# PAPI_M2_Control.net
KiCad netlist of a schematic drawn in Altium Designer
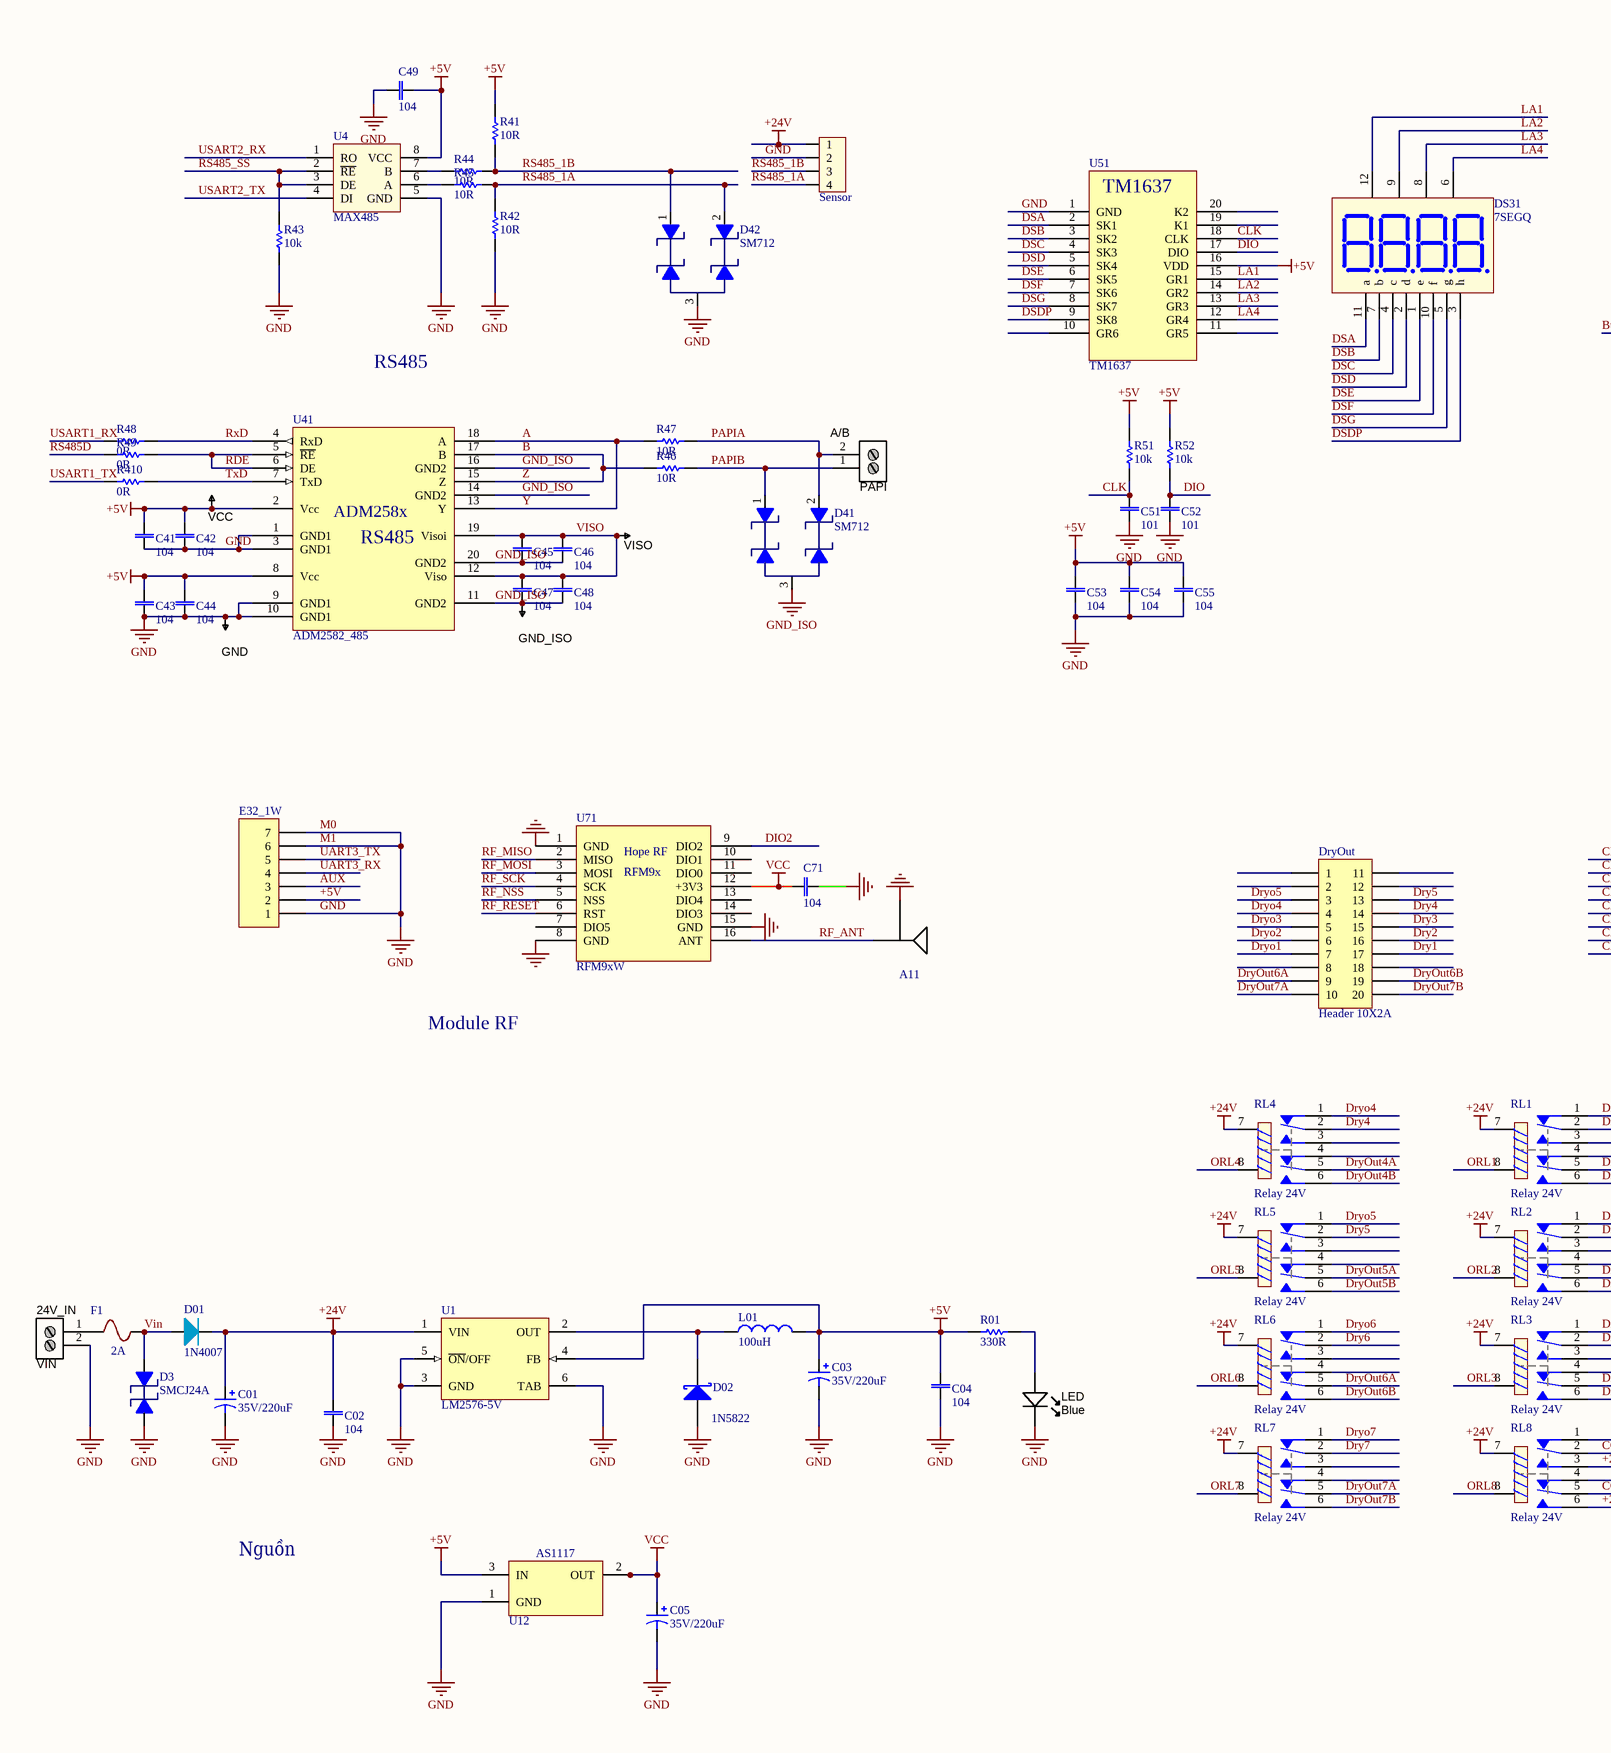
[diagram p0: PAPI_M2_Control.SchDoc, left]
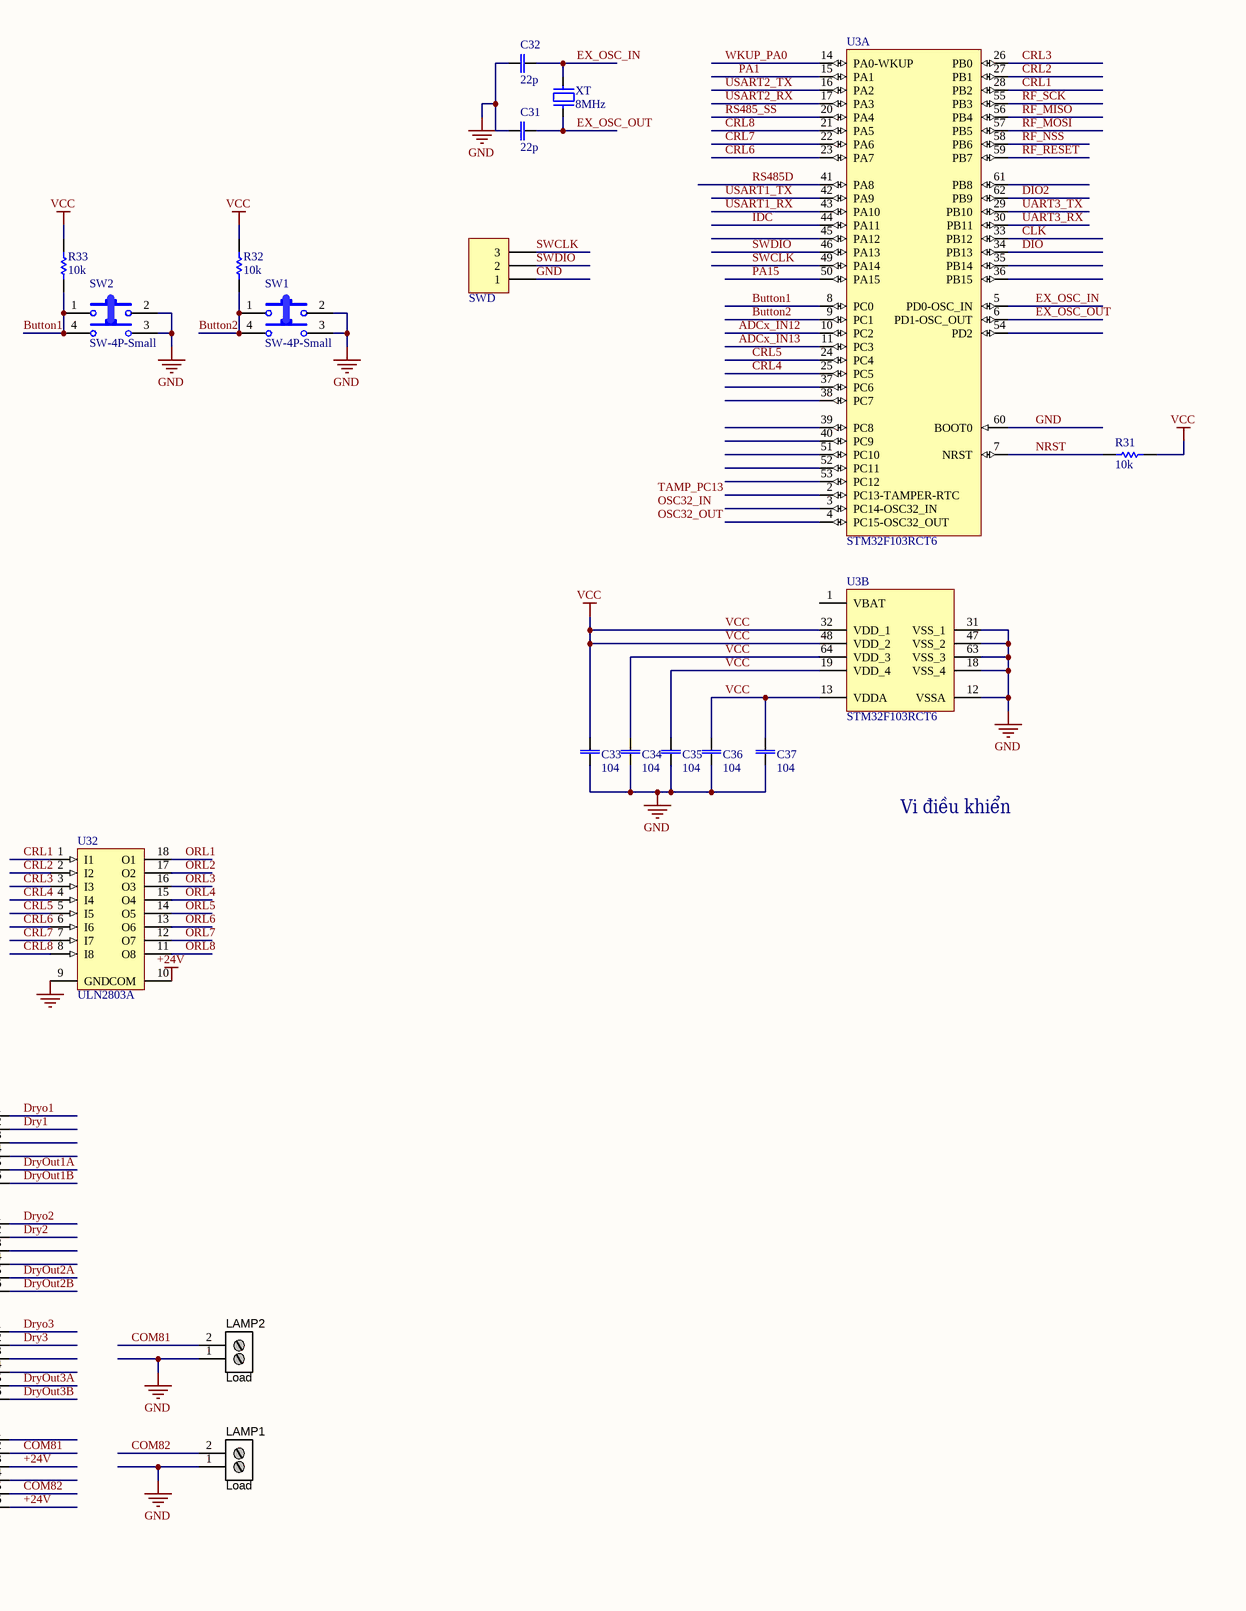
[diagram p1: PAPI_M2_Control.SchDoc, right]

(export (version "E")
  (design (tool "Eeschema 10.0.6"))
  (components
    (comp (ref "24V_IN")
      (value "VIN")
      (footprint "2P_PCB1")
      (description "Terminal Block Screw Type THT 2-Position 3.81mm pitch")
      (libsource (lib "") (part "2P_ScrewTerm_90S_3.81MM_1"))
    )
    (comp (ref "A11") (value "Giắc anten SMA") (footprint "SMA") (libsource (lib "Tuan") (part "RF_SMA")))
    (comp (ref "C01")
      (value "35V/220uF")
      (footprint "CAPE3.5-5.0MM_Rad_10x14mm")
      (fields (field (name "Comment") "Tụ nhôm cắm35V/220uF"))
      (libsource (lib "Tuan") (part "Cap"))
    )
    (comp (ref "C02")
      (value "104")
      (footprint "swatpcblib:CAP 0805")
      (description "Capacitor non polarized")
      (fields (field (name "Comment") "Tụ điện dán 0603104"))
      (libsource (lib "swatpcblib") (part "CAP NP"))
    )
    (comp (ref "C03")
      (value "35V/220uF")
      (footprint "CAPE3.5-5.0MM_Rad_10x14mm")
      (fields (field (name "Comment") "Tụ nhôm cắm35V/220uF"))
      (libsource (lib "Tuan") (part "Cap"))
    )
    (comp (ref "C04")
      (value "104")
      (footprint "swatpcblib:CAP 0805")
      (description "Capacitor non polarized")
      (fields (field (name "Comment") "Tụ điện dán 0603104"))
      (libsource (lib "swatpcblib") (part "CAP NP"))
    )
    (comp (ref "C05")
      (value "35V/220uF")
      (footprint "CAPE3.5-5.0MM_Rad_10x14mm")
      (fields (field (name "Comment") "Tụ nhôm cắm35V/220uF"))
      (libsource (lib "Tuan") (part "Cap"))
    )
    (comp (ref "C31")
      (value "22p")
      (footprint "swatpcblib:CAP 0805")
      (description "Capacitor non polarized")
      (fields (field (name "Comment") "Tụ điện dán 060322p"))
      (libsource (lib "swatpcblib") (part "CAP NP"))
    )
    (comp (ref "C32")
      (value "22p")
      (footprint "swatpcblib:CAP 0805")
      (description "Capacitor non polarized")
      (fields (field (name "Comment") "Tụ điện dán 060322p"))
      (libsource (lib "swatpcblib") (part "CAP NP"))
    )
    (comp (ref "C33")
      (value "104")
      (footprint "swatpcblib:CAP 0805")
      (description "Capacitor non polarized")
      (fields (field (name "Comment") "Tụ điện dán 0603104"))
      (libsource (lib "swatpcblib") (part "CAP NP"))
    )
    (comp (ref "C34")
      (value "104")
      (footprint "swatpcblib:CAP 0805")
      (description "Capacitor non polarized")
      (fields (field (name "Comment") "Tụ điện dán 0603104"))
      (libsource (lib "swatpcblib") (part "CAP NP"))
    )
    (comp (ref "C35")
      (value "104")
      (footprint "swatpcblib:CAP 0805")
      (description "Capacitor non polarized")
      (fields (field (name "Comment") "Tụ điện dán 0603104"))
      (libsource (lib "swatpcblib") (part "CAP NP"))
    )
    (comp (ref "C36")
      (value "104")
      (footprint "swatpcblib:CAP 0805")
      (description "Capacitor non polarized")
      (fields (field (name "Comment") "Tụ điện dán 0603104"))
      (libsource (lib "swatpcblib") (part "CAP NP"))
    )
    (comp (ref "C37")
      (value "104")
      (footprint "swatpcblib:CAP 0805")
      (description "Capacitor non polarized")
      (fields (field (name "Comment") "Tụ điện dán 0603104"))
      (libsource (lib "swatpcblib") (part "CAP NP"))
    )
    (comp (ref "C41")
      (value "104")
      (footprint "swatpcblib:CAP 0805")
      (description "Capacitor non polarized")
      (fields (field (name "Comment") "Tụ điện dán 0603104"))
      (libsource (lib "swatpcblib") (part "CAP NP"))
    )
    (comp (ref "C42")
      (value "104")
      (footprint "swatpcblib:CAP 0805")
      (description "Capacitor non polarized")
      (fields (field (name "Comment") "Tụ điện dán 0603104"))
      (libsource (lib "swatpcblib") (part "CAP NP"))
    )
    (comp (ref "C43")
      (value "104")
      (footprint "swatpcblib:CAP 0805")
      (description "Capacitor non polarized")
      (fields (field (name "Comment") "Tụ điện dán 0603104"))
      (libsource (lib "swatpcblib") (part "CAP NP"))
    )
    (comp (ref "C44")
      (value "104")
      (footprint "swatpcblib:CAP 0805")
      (description "Capacitor non polarized")
      (fields (field (name "Comment") "Tụ điện dán 0603104"))
      (libsource (lib "swatpcblib") (part "CAP NP"))
    )
    (comp (ref "C45")
      (value "104")
      (footprint "swatpcblib:CAP 0805")
      (description "Capacitor non polarized")
      (fields (field (name "Comment") "Tụ điện dán 0603104"))
      (libsource (lib "swatpcblib") (part "CAP NP"))
    )
    (comp (ref "C46")
      (value "104")
      (footprint "swatpcblib:CAP 0805")
      (description "Capacitor non polarized")
      (fields (field (name "Comment") "Tụ điện dán 0603104"))
      (libsource (lib "swatpcblib") (part "CAP NP"))
    )
    (comp (ref "C47")
      (value "104")
      (footprint "swatpcblib:CAP 0805")
      (description "Capacitor non polarized")
      (fields (field (name "Comment") "Tụ điện dán 0603104"))
      (libsource (lib "swatpcblib") (part "CAP NP"))
    )
    (comp (ref "C48")
      (value "104")
      (footprint "swatpcblib:CAP 0805")
      (description "Capacitor non polarized")
      (fields (field (name "Comment") "Tụ điện dán 0603104"))
      (libsource (lib "swatpcblib") (part "CAP NP"))
    )
    (comp (ref "C49")
      (value "104")
      (footprint "swatpcblib:CAP 0805")
      (description "Capacitor non polarized")
      (fields (field (name "Comment") "Tụ điện dán 0603104"))
      (libsource (lib "swatpcblib") (part "CAP NP"))
    )
    (comp (ref "C51")
      (value "101")
      (footprint "swatpcblib:CAP 0805")
      (description "Capacitor non polarized")
      (fields (field (name "Comment") "Tụ điện dán 0603101"))
      (libsource (lib "swatpcblib") (part "CAP NP"))
    )
    (comp (ref "C52")
      (value "101")
      (footprint "swatpcblib:CAP 0805")
      (description "Capacitor non polarized")
      (fields (field (name "Comment") "Tụ điện dán 0603101"))
      (libsource (lib "swatpcblib") (part "CAP NP"))
    )
    (comp (ref "C53")
      (value "104")
      (footprint "swatpcblib:CAP 0805")
      (description "Capacitor non polarized")
      (fields (field (name "Comment") "Tụ điện dán 0603104"))
      (libsource (lib "swatpcblib") (part "CAP NP"))
    )
    (comp (ref "C54")
      (value "104")
      (footprint "swatpcblib:CAP 0805")
      (description "Capacitor non polarized")
      (fields (field (name "Comment") "Tụ điện dán 0603104"))
      (libsource (lib "swatpcblib") (part "CAP NP"))
    )
    (comp (ref "C55")
      (value "104")
      (footprint "swatpcblib:CAP 0805")
      (description "Capacitor non polarized")
      (fields (field (name "Comment") "Tụ điện dán 0603104"))
      (libsource (lib "swatpcblib") (part "CAP NP"))
    )
    (comp (ref "C71")
      (value "104")
      (footprint "swatpcblib:CAP 0805")
      (description "Capacitor non polarized")
      (fields (field (name "Comment") "Tụ điện dán 0603104"))
      (libsource (lib "swatpcblib") (part "CAP NP"))
    )
    (comp (ref "D01")
      (value "Đi ốt cắm1N4007")
      (footprint "swatpcblib:DO-41")
      (fields (field (name "VL1") "1N4007"))
      (libsource (lib "swatpcblib") (part "Diode"))
    )
    (comp (ref "D02")
      (value "1N5822")
      (footprint "swatpcblib:DO-201")
      (description "Schottky Diodes Through Hole 3 A 40 V Schottky Diodes, DO-201AD, SB340 ,MBR340")
      (fields (field (name "Comment") "Đi ốt cắm1N5822"))
      (libsource (lib "swatpcblib") (part "Schottky Diodes"))
    )
    (comp (ref "D3")
      (value "SMCJ24A")
      (footprint "PBL - SMD Packages:DO-214AB")
      (description "ESD Suppressors / TVS Diodes 24volts 1.5kW 5% Uni-Dir. AEC-Q101")
      (libsource (lib "swatpcblib") (part "Diode Zenner"))
    )
    (comp (ref "D41") (value "SM712") (footprint "SOT23 TOP") (libsource (lib "Tuan") (part "SM712")))
    (comp (ref "D42") (value "SM712") (footprint "SOT23 TOP") (libsource (lib "Tuan") (part "SM712")))
    (comp (ref "DryOut")
      (value "Header 10X2A")
      (footprint "heromap:HDR2X10_CEN")
      (description "Header, 10-Pin, Dual row")
      (fields (field (name "PUBLISHER") "Altium Limited"))
      (libsource (lib "heromap") (part "Header 10X2A"))
    )
    (comp (ref "DS31")
      (value "7SEGQ")
      (footprint "heromap:7SEGQ")
      (description "Four 7 Seg Dipslay")
      (libsource (lib "heromap") (part "LED7Q"))
    )
    (comp (ref "E32_1W")
      (value "Header 7")
      (footprint "RF_AS32")
      (description "Header, 7-Pin")
      (fields (field (name "PUBLISHER") "Altium Limited"))
      (libsource (lib "Miscellaneous Connectors") (part "Header 7"))
    )
    (comp (ref "F1") (value "2A") (footprint "Fuse") (libsource (lib "Tuan") (part "Fuse")))
    (comp (ref "GND")
      (value "TESTPOINT")
      (footprint "TP-R60")
      (description "SMD test pin")
      (libsource (lib "PBL - Test Points") (part "TESTPOINT"))
    )
    (comp (ref "GND_ISO")
      (value "TESTPOINT")
      (footprint "TP-R60")
      (description "SMD test pin")
      (libsource (lib "PBL - Test Points") (part "TESTPOINT"))
    )
    (comp (ref "L01")
      (value "100uH")
      (footprint "Inductor 12x12x6")
      (fields (field (name "Comment") "Cuộn cảm dán100uH"))
      (libsource (lib "swatpcblib") (part "Inductor"))
    )
    (comp (ref "LAMP1")
      (value "Load")
      (footprint "2P_PCB1")
      (description "Terminal Block Screw Type THT 2-Position 3.81mm pitch")
      (libsource (lib "PBL - Connectors") (part "2P_ScrewTerm_90S_3.81MM"))
    )
    (comp (ref "LAMP2")
      (value "Load")
      (footprint "2P_PCB1")
      (description "Terminal Block Screw Type THT 2-Position 3.81mm pitch")
      (libsource (lib "PBL - Connectors") (part "2P_ScrewTerm_90S_3.81MM"))
    )
    (comp (ref "LED")
      (value "Blue")
      (footprint "LED-0805-K")
      (description "LED 0805 SMD Blue 100mcd 470nm")
      (fields (field (name "COLOR") "Blue"))
      (libsource (lib "PBL - Light Sources") (part "LED_SMD_Blue_0805_100mcd"))
    )
    (comp (ref "PAPI")
      (value "A/B")
      (footprint "2P_PCB1")
      (description "Terminal Block Screw Type THT 2-Position 3.81mm pitch")
      (libsource (lib "PBL - Connectors") (part "2P_ScrewTerm_90S_3.81MM"))
    )
    (comp (ref "R01")
      (value "330R")
      (footprint "swatpcblib:RES 0805")
      (description "Resistor")
      (fields (field (name "Comment") "Điện trở dán 0603330R"))
      (libsource (lib "swatpcblib") (part "Res"))
    )
    (comp (ref "R31")
      (value "10k")
      (footprint "swatpcblib:RES 0805")
      (description "Resistor")
      (fields (field (name "Comment") "Điện trở dán 060310k"))
      (libsource (lib "swatpcblib") (part "Res"))
    )
    (comp (ref "R32")
      (value "10k")
      (footprint "swatpcblib:RES 0805")
      (description "Resistor")
      (fields (field (name "Comment") "Điện trở dán 060310k"))
      (libsource (lib "swatpcblib") (part "Res"))
    )
    (comp (ref "R33")
      (value "10k")
      (footprint "swatpcblib:RES 0805")
      (description "Resistor")
      (fields (field (name "Comment") "Điện trở dán 060310k"))
      (libsource (lib "swatpcblib") (part "Res"))
    )
    (comp (ref "R41")
      (value "10R")
      (footprint "swatpcblib:RES 0805")
      (description "Resistor")
      (fields (field (name "Comment") "Điện trở dán 060310R"))
      (libsource (lib "swatpcblib") (part "Res"))
    )
    (comp (ref "R42")
      (value "10R")
      (footprint "swatpcblib:RES 0805")
      (description "Resistor")
      (fields (field (name "Comment") "Điện trở dán 060310R"))
      (libsource (lib "swatpcblib") (part "Res"))
    )
    (comp (ref "R43")
      (value "10k")
      (footprint "swatpcblib:RES 0805")
      (description "Resistor")
      (fields (field (name "Comment") "Điện trở dán 060310k"))
      (libsource (lib "swatpcblib") (part "Res"))
    )
    (comp (ref "R44")
      (value "10R")
      (footprint "swatpcblib:RES 0805")
      (description "Resistor")
      (fields (field (name "Comment") "Điện trở dán 060310R"))
      (libsource (lib "swatpcblib") (part "Res"))
    )
    (comp (ref "R45")
      (value "10R")
      (footprint "swatpcblib:RES 0805")
      (description "Resistor")
      (fields (field (name "Comment") "Điện trở dán 060310R"))
      (libsource (lib "swatpcblib") (part "Res"))
    )
    (comp (ref "R46")
      (value "10R")
      (footprint "swatpcblib:RES 0805")
      (description "Resistor")
      (fields (field (name "Comment") "Điện trở dán 060310R"))
      (libsource (lib "swatpcblib") (part "Res"))
    )
    (comp (ref "R47")
      (value "10R")
      (footprint "swatpcblib:RES 0805")
      (description "Resistor")
      (fields (field (name "Comment") "Điện trở dán 060310R"))
      (libsource (lib "swatpcblib") (part "Res"))
    )
    (comp (ref "R48")
      (value "0R")
      (footprint "swatpcblib:RES 0805")
      (description "Resistor")
      (fields (field (name "Comment") "Điện trở dán 08050R"))
      (libsource (lib "swatpcblib") (part "Res"))
    )
    (comp (ref "R49")
      (value "0R")
      (footprint "swatpcblib:RES 0805")
      (description "Resistor")
      (fields (field (name "Comment") "Điện trở dán 06030R"))
      (libsource (lib "swatpcblib") (part "Res"))
    )
    (comp (ref "R51")
      (value "10k")
      (footprint "swatpcblib:RES 0805")
      (description "Resistor")
      (fields (field (name "Comment") "Điện trở dán 060310k"))
      (libsource (lib "swatpcblib") (part "Res"))
    )
    (comp (ref "R52")
      (value "10k")
      (footprint "swatpcblib:RES 0805")
      (description "Resistor")
      (fields (field (name "Comment") "Điện trở dán 060310k"))
      (libsource (lib "swatpcblib") (part "Res"))
    )
    (comp (ref "R410")
      (value "0R")
      (footprint "swatpcblib:RES 0805")
      (description "Resistor")
      (fields (field (name "Comment") "Điện trở dán 06030R"))
      (libsource (lib "swatpcblib") (part "Res"))
    )
    (comp (ref "RL1")
      (value "Relay 24V")
      (footprint "RL_DPDT_1A")
      (description "Relay DPDT")
      (libsource (lib "Download") (part "Relay 2"))
    )
    (comp (ref "RL2")
      (value "Relay 24V")
      (footprint "RL_DPDT_1A")
      (description "Relay DPDT")
      (libsource (lib "Download") (part "Relay 2"))
    )
    (comp (ref "RL3")
      (value "Relay 24V")
      (footprint "RL_DPDT_1A")
      (description "Relay DPDT")
      (libsource (lib "Download") (part "Relay 2"))
    )
    (comp (ref "RL4")
      (value "Relay 24V")
      (footprint "RL_DPDT_1A")
      (description "Relay DPDT")
      (libsource (lib "Download") (part "Relay 2"))
    )
    (comp (ref "RL5")
      (value "Relay 24V")
      (footprint "RL_DPDT_1A")
      (description "Relay DPDT")
      (libsource (lib "Download") (part "Relay 2"))
    )
    (comp (ref "RL6")
      (value "Relay 24V")
      (footprint "RL_DPDT_1A")
      (description "Relay DPDT")
      (libsource (lib "Download") (part "Relay 2"))
    )
    (comp (ref "RL7")
      (value "Relay 24V")
      (footprint "RL_DPDT_1A")
      (description "Relay DPDT")
      (libsource (lib "Download") (part "Relay 2"))
    )
    (comp (ref "RL8")
      (value "Relay 24V")
      (footprint "RL_DPDT_1A")
      (description "Relay DPDT")
      (libsource (lib "Download") (part "Relay 2"))
    )
    (comp (ref "Sensor")
      (value "JP4")
      (footprint "heromap:CON4")
      (description "Connector 4")
      (libsource (lib "heromap") (part "Con4"))
    )
    (comp (ref "SW1") (value "SW-4P-Small") (footprint "SW") (libsource (lib "Tuan") (part "SW-4P-Small")))
    (comp (ref "SW2") (value "SW-4P-Small") (footprint "SW") (libsource (lib "Tuan") (part "SW-4P-Small")))
    (comp (ref "SWD")
      (value "Header 3")
      (footprint "heromap:HDR1X3")
      (description "Header, 3-Pin")
      (fields (field (name "PUBLISHER") "Altium Limited"))
      (libsource (lib "heromap") (part "Header 3"))
    )
    (comp (ref "U1")
      (value "LM2576-5V")
      (footprint "TS5B_N")
      (description "SIMPLE SWITCHER Power Converter 150 KHz 3A Step-Down Voltage Regulator")
      (fields
        (field (name "MANUFACTURER") "National Semiconductor")
        (field (name "DIGIKEYPARTNUMBER") "LM2596S-ADJ-ND")
        (field (name "PUBLISHER") "Altium Limited")
      )
      (libsource (lib "NSC Switcher") (part "LM2596S-ADJ"))
    )
    (comp (ref "U3")
      (value "STM32F103RCT6")
      (footprint "LQFP64_Tuan")
      (libsource (lib "STMicroelectronics STM32 F1") (part "STM32F103RCT6"))
    )
    (comp (ref "U4")
      (value "MAX485")
      (footprint "SOIC 8")
      (description "RS232 - RS485 (Same sn75176)")
      (libsource (lib "heromap") (part "MAX485"))
    )
    (comp (ref "U12") (value "AS1117") (footprint "SOT223-4N") (libsource (lib "Tuan") (part "AS1117")))
    (comp (ref "U32")
      (value "ULN2803A")
      (footprint "SOIC-18")
      (description "High-Voltage, High-Current Darlington Array")
      (fields (field (name "PUBLISHER") "Altium Limited"))
      (libsource (lib "syhaunguyen") (part "ULN2803A"))
    )
    (comp (ref "U41")
      (value "ADM2582_485")
      (footprint "syhaunguyen:SO-20B")
      (libsource (lib "Tuan") (part "ADM2582_485"))
    )
    (comp (ref "U51") (value "TM1637") (footprint "SOIC-20") (libsource (lib "Tuan") (part "TM1637")))
    (comp (ref "U71") (value "RFM9xW") (footprint "RFM9xW") (libsource (lib "Tuan") (part "RFM9xW")))
    (comp (ref "VCC")
      (value "TESTPOINT")
      (footprint "TP-R60")
      (description "SMD test pin")
      (libsource (lib "PBL - Test Points") (part "TESTPOINT"))
    )
    (comp (ref "VISO")
      (value "TESTPOINT")
      (footprint "TP-R60")
      (description "SMD test pin")
      (libsource (lib "PBL - Test Points") (part "TESTPOINT"))
    )
    (comp (ref "XT") (value "8MHz") (footprint "XT2") (libsource (lib "Tuan") (part "Crystal")))
  )
  (nets
    (net (code "1") (name "+5V") (class "Default")
      (node (ref "C03") (pin "1") (pinfunction "1_1") (pintype "passive"))
      (node (ref "C04") (pin "2") (pinfunction "2_2") (pintype "passive"))
      (node (ref "C41") (pin "2") (pinfunction "2_2") (pintype "passive"))
      (node (ref "C42") (pin "2") (pinfunction "2_2") (pintype "passive"))
      (node (ref "C43") (pin "2") (pinfunction "2_2") (pintype "passive"))
      (node (ref "C44") (pin "2") (pinfunction "2_2") (pintype "passive"))
      (node (ref "C49") (pin "1") (pinfunction "1_1") (pintype "passive"))
      (node (ref "C53") (pin "2") (pinfunction "2_2") (pintype "passive"))
      (node (ref "C54") (pin "2") (pinfunction "2_2") (pintype "passive"))
      (node (ref "C55") (pin "2") (pinfunction "2_2") (pintype "passive"))
      (node (ref "E32_1W") (pin "2") (pinfunction "2_2") (pintype "passive"))
      (node (ref "L01") (pin "2") (pinfunction "2_2") (pintype "passive"))
      (node (ref "R01") (pin "2") (pinfunction "2_2") (pintype "passive"))
      (node (ref "R41") (pin "2") (pinfunction "2_2") (pintype "passive"))
      (node (ref "R51") (pin "2") (pinfunction "2_2") (pintype "passive"))
      (node (ref "R52") (pin "2") (pinfunction "2_2") (pintype "passive"))
      (node (ref "U1") (pin "4") (pinfunction "FB_4") (pintype "input"))
      (node (ref "U12") (pin "3") (pinfunction "IN_3") (pintype "power_in"))
      (node (ref "U4") (pin "8") (pinfunction "VCC_8") (pintype "passive"))
      (node (ref "U41") (pin "2") (pinfunction "Vcc_2") (pintype "power_in"))
      (node (ref "U41") (pin "8") (pinfunction "Vcc_8") (pintype "power_in"))
      (node (ref "U51") (pin "16") (pinfunction "VDD_16") (pintype "passive"))
      (node (ref "VCC") (pin "1") (pintype "passive"))
    )
    (net (code "2") (name "+24V") (class "Default")
      (node (ref "C01") (pin "1") (pinfunction "1_1") (pintype "passive"))
      (node (ref "C02") (pin "2") (pinfunction "2_2") (pintype "passive"))
      (node (ref "D01") (pin "K") (pinfunction "K_K") (pintype "passive"))
      (node (ref "RL1") (pin "7") (pinfunction "7_7") (pintype "passive"))
      (node (ref "RL2") (pin "7") (pinfunction "7_7") (pintype "passive"))
      (node (ref "RL3") (pin "7") (pinfunction "7_7") (pintype "passive"))
      (node (ref "RL4") (pin "7") (pinfunction "7_7") (pintype "passive"))
      (node (ref "RL5") (pin "7") (pinfunction "7_7") (pintype "passive"))
      (node (ref "RL6") (pin "7") (pinfunction "7_7") (pintype "passive"))
      (node (ref "RL7") (pin "7") (pinfunction "7_7") (pintype "passive"))
      (node (ref "RL8") (pin "3") (pinfunction "3_3") (pintype "passive"))
      (node (ref "RL8") (pin "6") (pinfunction "6_6") (pintype "passive"))
      (node (ref "RL8") (pin "7") (pinfunction "7_7") (pintype "passive"))
      (node (ref "Sensor") (pin "1") (pinfunction "1_1") (pintype "passive"))
      (node (ref "U1") (pin "1") (pinfunction "VIN_1") (pintype "power_in"))
      (node (ref "U32") (pin "10") (pinfunction "COM_10") (pintype "passive"))
    )
    (net (code "3") (name "/A") (class "Default")
      (node (ref "R47") (pin "1") (pinfunction "1_1") (pintype "passive"))
      (node (ref "U41") (pin "13") (pinfunction "Y_13") (pintype "passive"))
      (node (ref "U41") (pin "18") (pinfunction "A_18") (pintype "passive"))
    )
    (net (code "4") (name "/ADCx_IN12") (class "Default")
      (node (ref "U3") (pin "10") (pinfunction "PC2_10") (pintype "bidirectional"))
    )
    (net (code "5") (name "/ADCx_IN13") (class "Default")
      (node (ref "U3") (pin "11") (pinfunction "PC3_11") (pintype "bidirectional"))
    )
    (net (code "6") (name "/AUX") (class "Default")
      (node (ref "E32_1W") (pin "3") (pinfunction "3_3") (pintype "passive"))
    )
    (net (code "7") (name "/B") (class "Default")
      (node (ref "R46") (pin "1") (pinfunction "1_1") (pintype "passive"))
      (node (ref "U41") (pin "15") (pinfunction "Z_15") (pintype "passive"))
      (node (ref "U41") (pin "17") (pinfunction "B_17") (pintype "passive"))
    )
    (net (code "8") (name "/Button1") (class "Default")
      (node (ref "R33") (pin "1") (pinfunction "1_1") (pintype "passive"))
      (node (ref "SW2") (pin "1") (pinfunction "1_1") (pintype "passive"))
      (node (ref "SW2") (pin "4") (pinfunction "4_4") (pintype "passive"))
      (node (ref "U3") (pin "8") (pinfunction "PC0_8") (pintype "bidirectional"))
    )
    (net (code "9") (name "/Button2") (class "Default")
      (node (ref "R32") (pin "1") (pinfunction "1_1") (pintype "passive"))
      (node (ref "SW1") (pin "1") (pinfunction "1_1") (pintype "passive"))
      (node (ref "SW1") (pin "4") (pinfunction "4_4") (pintype "passive"))
      (node (ref "U3") (pin "9") (pinfunction "PC1_9") (pintype "bidirectional"))
    )
    (net (code "10") (name "/CLK") (class "Default")
      (node (ref "C51") (pin "2") (pinfunction "2_2") (pintype "passive"))
      (node (ref "R51") (pin "1") (pinfunction "1_1") (pintype "passive"))
      (node (ref "U3") (pin "33") (pinfunction "PB12_33") (pintype "bidirectional"))
      (node (ref "U51") (pin "18") (pinfunction "CLK_18") (pintype "passive"))
    )
    (net (code "11") (name "/COM81") (class "Default")
      (node (ref "LAMP2") (pin "2") (pinfunction "2_2") (pintype "passive"))
      (node (ref "RL8") (pin "2") (pinfunction "2_2") (pintype "passive"))
    )
    (net (code "12") (name "/COM82") (class "Default")
      (node (ref "LAMP1") (pin "2") (pinfunction "2_2") (pintype "passive"))
      (node (ref "RL8") (pin "5") (pinfunction "5_5") (pintype "passive"))
    )
    (net (code "13") (name "/CRL1") (class "Default")
      (node (ref "U3") (pin "28") (pinfunction "PB2_28") (pintype "bidirectional"))
      (node (ref "U32") (pin "1") (pinfunction "I1_1") (pintype "input"))
    )
    (net (code "14") (name "/CRL2") (class "Default")
      (node (ref "U3") (pin "27") (pinfunction "PB1_27") (pintype "bidirectional"))
      (node (ref "U32") (pin "2") (pinfunction "I2_2") (pintype "input"))
    )
    (net (code "15") (name "/CRL3") (class "Default")
      (node (ref "U3") (pin "26") (pinfunction "PB0_26") (pintype "bidirectional"))
      (node (ref "U32") (pin "3") (pinfunction "I3_3") (pintype "input"))
    )
    (net (code "16") (name "/CRL4") (class "Default")
      (node (ref "U3") (pin "25") (pinfunction "PC5_25") (pintype "bidirectional"))
      (node (ref "U32") (pin "4") (pinfunction "I4_4") (pintype "input"))
    )
    (net (code "17") (name "/CRL5") (class "Default")
      (node (ref "U3") (pin "24") (pinfunction "PC4_24") (pintype "bidirectional"))
      (node (ref "U32") (pin "5") (pinfunction "I5_5") (pintype "input"))
    )
    (net (code "18") (name "/CRL6") (class "Default")
      (node (ref "U3") (pin "23") (pinfunction "PA7_23") (pintype "bidirectional"))
      (node (ref "U32") (pin "6") (pinfunction "I6_6") (pintype "input"))
    )
    (net (code "19") (name "/CRL7") (class "Default")
      (node (ref "U3") (pin "22") (pinfunction "PA6_22") (pintype "bidirectional"))
      (node (ref "U32") (pin "7") (pinfunction "I7_7") (pintype "input"))
    )
    (net (code "20") (name "/CRL8") (class "Default")
      (node (ref "U3") (pin "21") (pinfunction "PA5_21") (pintype "bidirectional"))
      (node (ref "U32") (pin "8") (pinfunction "I8_8") (pintype "input"))
    )
    (net (code "21") (name "/DIO") (class "Default")
      (node (ref "C52") (pin "2") (pinfunction "2_2") (pintype "passive"))
      (node (ref "R52") (pin "1") (pinfunction "1_1") (pintype "passive"))
      (node (ref "U3") (pin "34") (pinfunction "PB13_34") (pintype "bidirectional"))
      (node (ref "U51") (pin "17") (pinfunction "DIO_17") (pintype "passive"))
    )
    (net (code "22") (name "/DIO2") (class "Default")
      (node (ref "U3") (pin "62") (pinfunction "PB9_62") (pintype "bidirectional"))
      (node (ref "U71") (pin "9") (pinfunction "DIO2_9") (pintype "passive"))
    )
    (net (code "23") (name "/DSA") (class "Default")
      (node (ref "DS31") (pin "11") (pinfunction "a_11") (pintype "passive"))
      (node (ref "U51") (pin "2") (pinfunction "SK1_2") (pintype "passive"))
    )
    (net (code "24") (name "/DSB") (class "Default")
      (node (ref "DS31") (pin "7") (pinfunction "b_7") (pintype "passive"))
      (node (ref "U51") (pin "3") (pinfunction "SK2_3") (pintype "passive"))
    )
    (net (code "25") (name "/DSC") (class "Default")
      (node (ref "DS31") (pin "4") (pinfunction "c_4") (pintype "passive"))
      (node (ref "U51") (pin "4") (pinfunction "SK3_4") (pintype "passive"))
    )
    (net (code "26") (name "/DSD") (class "Default")
      (node (ref "DS31") (pin "2") (pinfunction "d_2") (pintype "passive"))
      (node (ref "U51") (pin "5") (pinfunction "SK4_5") (pintype "passive"))
    )
    (net (code "27") (name "/DSDP") (class "Default")
      (node (ref "DS31") (pin "3") (pinfunction "h_3") (pintype "passive"))
      (node (ref "U51") (pin "9") (pinfunction "SK8_9") (pintype "passive"))
    )
    (net (code "28") (name "/DSE") (class "Default")
      (node (ref "DS31") (pin "1") (pinfunction "e_1") (pintype "passive"))
      (node (ref "U51") (pin "6") (pinfunction "SK5_6") (pintype "passive"))
    )
    (net (code "29") (name "/DSF") (class "Default")
      (node (ref "DS31") (pin "10") (pinfunction "f_10") (pintype "passive"))
      (node (ref "U51") (pin "7") (pinfunction "SK6_7") (pintype "passive"))
    )
    (net (code "30") (name "/DSG") (class "Default")
      (node (ref "DS31") (pin "5") (pinfunction "g_5") (pintype "passive"))
      (node (ref "U51") (pin "8") (pinfunction "SK7_8") (pintype "passive"))
    )
    (net (code "31") (name "/Dry1") (class "Default")
      (node (ref "DryOut") (pin "17") (pinfunction "17_17") (pintype "passive"))
      (node (ref "RL1") (pin "2") (pinfunction "2_2") (pintype "passive"))
    )
    (net (code "32") (name "/Dry2") (class "Default")
      (node (ref "DryOut") (pin "16") (pinfunction "16_16") (pintype "passive"))
      (node (ref "RL2") (pin "2") (pinfunction "2_2") (pintype "passive"))
    )
    (net (code "33") (name "/Dry3") (class "Default")
      (node (ref "DryOut") (pin "15") (pinfunction "15_15") (pintype "passive"))
      (node (ref "RL3") (pin "2") (pinfunction "2_2") (pintype "passive"))
    )
    (net (code "34") (name "/Dry4") (class "Default")
      (node (ref "DryOut") (pin "14") (pinfunction "14_14") (pintype "passive"))
      (node (ref "RL4") (pin "2") (pinfunction "2_2") (pintype "passive"))
    )
    (net (code "35") (name "/Dry5") (class "Default")
      (node (ref "DryOut") (pin "13") (pinfunction "13_13") (pintype "passive"))
      (node (ref "RL5") (pin "2") (pinfunction "2_2") (pintype "passive"))
    )
    (net (code "36") (name "/Dry6") (class "Default")
      (node (ref "RL6") (pin "2") (pinfunction "2_2") (pintype "passive"))
    )
    (net (code "37") (name "/Dry7") (class "Default")
      (node (ref "RL7") (pin "2") (pinfunction "2_2") (pintype "passive"))
    )
    (net (code "38") (name "/DryOut1A") (class "Default")
      (node (ref "RL1") (pin "5") (pinfunction "5_5") (pintype "passive"))
    )
    (net (code "39") (name "/DryOut1B") (class "Default")
      (node (ref "RL1") (pin "6") (pinfunction "6_6") (pintype "passive"))
    )
    (net (code "40") (name "/DryOut2A") (class "Default")
      (node (ref "RL2") (pin "5") (pinfunction "5_5") (pintype "passive"))
    )
    (net (code "41") (name "/DryOut2B") (class "Default")
      (node (ref "RL2") (pin "6") (pinfunction "6_6") (pintype "passive"))
    )
    (net (code "42") (name "/DryOut3A") (class "Default")
      (node (ref "RL3") (pin "5") (pinfunction "5_5") (pintype "passive"))
    )
    (net (code "43") (name "/DryOut3B") (class "Default")
      (node (ref "RL3") (pin "6") (pinfunction "6_6") (pintype "passive"))
    )
    (net (code "44") (name "/DryOut4A") (class "Default")
      (node (ref "RL4") (pin "5") (pinfunction "5_5") (pintype "passive"))
    )
    (net (code "45") (name "/DryOut4B") (class "Default")
      (node (ref "RL4") (pin "6") (pinfunction "6_6") (pintype "passive"))
    )
    (net (code "46") (name "/DryOut5A") (class "Default")
      (node (ref "RL5") (pin "5") (pinfunction "5_5") (pintype "passive"))
    )
    (net (code "47") (name "/DryOut5B") (class "Default")
      (node (ref "RL5") (pin "6") (pinfunction "6_6") (pintype "passive"))
    )
    (net (code "48") (name "/DryOut6A") (class "Default")
      (node (ref "DryOut") (pin "9") (pinfunction "9_9") (pintype "passive"))
      (node (ref "RL6") (pin "5") (pinfunction "5_5") (pintype "passive"))
    )
    (net (code "49") (name "/DryOut6B") (class "Default")
      (node (ref "DryOut") (pin "19") (pinfunction "19_19") (pintype "passive"))
      (node (ref "RL6") (pin "6") (pinfunction "6_6") (pintype "passive"))
    )
    (net (code "50") (name "/DryOut7A") (class "Default")
      (node (ref "DryOut") (pin "10") (pinfunction "10_10") (pintype "passive"))
      (node (ref "RL7") (pin "5") (pinfunction "5_5") (pintype "passive"))
    )
    (net (code "51") (name "/DryOut7B") (class "Default")
      (node (ref "DryOut") (pin "20") (pinfunction "20_20") (pintype "passive"))
      (node (ref "RL7") (pin "6") (pinfunction "6_6") (pintype "passive"))
    )
    (net (code "52") (name "/Dryo1") (class "Default")
      (node (ref "DryOut") (pin "7") (pinfunction "7_7") (pintype "passive"))
      (node (ref "RL1") (pin "1") (pinfunction "1_1") (pintype "passive"))
    )
    (net (code "53") (name "/Dryo2") (class "Default")
      (node (ref "DryOut") (pin "6") (pinfunction "6_6") (pintype "passive"))
      (node (ref "RL2") (pin "1") (pinfunction "1_1") (pintype "passive"))
    )
    (net (code "54") (name "/Dryo3") (class "Default")
      (node (ref "DryOut") (pin "5") (pinfunction "5_5") (pintype "passive"))
      (node (ref "RL3") (pin "1") (pinfunction "1_1") (pintype "passive"))
    )
    (net (code "55") (name "/Dryo4") (class "Default")
      (node (ref "DryOut") (pin "4") (pinfunction "4_4") (pintype "passive"))
      (node (ref "RL4") (pin "1") (pinfunction "1_1") (pintype "passive"))
    )
    (net (code "56") (name "/Dryo5") (class "Default")
      (node (ref "DryOut") (pin "3") (pinfunction "3_3") (pintype "passive"))
      (node (ref "RL5") (pin "1") (pinfunction "1_1") (pintype "passive"))
    )
    (net (code "57") (name "/Dryo6") (class "Default")
      (node (ref "RL6") (pin "1") (pinfunction "1_1") (pintype "passive"))
    )
    (net (code "58") (name "/Dryo7") (class "Default")
      (node (ref "RL7") (pin "1") (pinfunction "1_1") (pintype "passive"))
    )
    (net (code "59") (name "/EX_OSC_IN") (class "Default")
      (node (ref "C32") (pin "2") (pinfunction "2_2") (pintype "passive"))
      (node (ref "U3") (pin "5") (pinfunction "PD0-OSC_IN_5") (pintype "bidirectional"))
      (node (ref "XT") (pin "2") (pinfunction "2_2") (pintype "passive"))
    )
    (net (code "60") (name "/EX_OSC_OUT") (class "Default")
      (node (ref "C31") (pin "2") (pinfunction "2_2") (pintype "passive"))
      (node (ref "U3") (pin "6") (pinfunction "PD1-OSC_OUT_6") (pintype "bidirectional"))
      (node (ref "XT") (pin "1") (pinfunction "1_1") (pintype "passive"))
    )
    (net (code "61") (name "/IDC") (class "Default")
      (node (ref "U3") (pin "44") (pinfunction "PA11_44") (pintype "bidirectional"))
    )
    (net (code "62") (name "/LA1") (class "Default")
      (node (ref "DS31") (pin "12") (pinfunction "V1_12") (pintype "passive"))
      (node (ref "U51") (pin "15") (pinfunction "GR1_15") (pintype "passive"))
    )
    (net (code "63") (name "/LA2") (class "Default")
      (node (ref "DS31") (pin "9") (pinfunction "V2_9") (pintype "passive"))
      (node (ref "U51") (pin "14") (pinfunction "GR2_14") (pintype "passive"))
    )
    (net (code "64") (name "/LA3") (class "Default")
      (node (ref "DS31") (pin "8") (pinfunction "V3_8") (pintype "passive"))
      (node (ref "U51") (pin "13") (pinfunction "GR3_13") (pintype "passive"))
    )
    (net (code "65") (name "/LA4") (class "Default")
      (node (ref "DS31") (pin "6") (pinfunction "V4_6") (pintype "passive"))
      (node (ref "U51") (pin "12") (pinfunction "GR4_12") (pintype "passive"))
    )
    (net (code "66") (name "/NRST") (class "Default")
      (node (ref "R31") (pin "1") (pinfunction "1_1") (pintype "passive"))
      (node (ref "U3") (pin "7") (pinfunction "NRST_7") (pintype "bidirectional"))
    )
    (net (code "67") (name "/ORL1") (class "Default")
      (node (ref "RL1") (pin "8") (pinfunction "8_8") (pintype "passive"))
      (node (ref "U32") (pin "18") (pinfunction "O1_18") (pintype "open_collector"))
    )
    (net (code "68") (name "/ORL2") (class "Default")
      (node (ref "RL2") (pin "8") (pinfunction "8_8") (pintype "passive"))
      (node (ref "U32") (pin "17") (pinfunction "O2_17") (pintype "open_collector"))
    )
    (net (code "69") (name "/ORL3") (class "Default")
      (node (ref "RL3") (pin "8") (pinfunction "8_8") (pintype "passive"))
      (node (ref "U32") (pin "16") (pinfunction "O3_16") (pintype "open_collector"))
    )
    (net (code "70") (name "/ORL4") (class "Default")
      (node (ref "RL4") (pin "8") (pinfunction "8_8") (pintype "passive"))
      (node (ref "U32") (pin "15") (pinfunction "O4_15") (pintype "open_collector"))
    )
    (net (code "71") (name "/ORL5") (class "Default")
      (node (ref "RL5") (pin "8") (pinfunction "8_8") (pintype "passive"))
      (node (ref "U32") (pin "14") (pinfunction "O5_14") (pintype "open_collector"))
    )
    (net (code "72") (name "/ORL6") (class "Default")
      (node (ref "RL6") (pin "8") (pinfunction "8_8") (pintype "passive"))
      (node (ref "U32") (pin "13") (pinfunction "O6_13") (pintype "open_collector"))
    )
    (net (code "73") (name "/ORL7") (class "Default")
      (node (ref "RL7") (pin "8") (pinfunction "8_8") (pintype "passive"))
      (node (ref "U32") (pin "12") (pinfunction "O7_12") (pintype "open_collector"))
    )
    (net (code "74") (name "/ORL8") (class "Default")
      (node (ref "RL8") (pin "8") (pinfunction "8_8") (pintype "passive"))
      (node (ref "U32") (pin "11") (pinfunction "O8_11") (pintype "open_collector"))
    )
    (net (code "77") (name "/PA1") (class "Default")
      (node (ref "U3") (pin "15") (pinfunction "PA1_15") (pintype "bidirectional"))
    )
    (net (code "78") (name "/PA15") (class "Default")
      (node (ref "U3") (pin "50") (pinfunction "PA15_50") (pintype "bidirectional"))
    )
    (net (code "79") (name "/PAPIA") (class "Default")
      (node (ref "D41") (pin "2") (pinfunction "IO2_2") (pintype "passive"))
      (node (ref "PAPI") (pin "2") (pinfunction "2_2") (pintype "passive"))
      (node (ref "R47") (pin "2") (pinfunction "2_2") (pintype "passive"))
    )
    (net (code "80") (name "/PAPIB") (class "Default")
      (node (ref "D41") (pin "1") (pinfunction "IO1_1") (pintype "passive"))
      (node (ref "PAPI") (pin "1") (pinfunction "1_1") (pintype "passive"))
      (node (ref "R46") (pin "2") (pinfunction "2_2") (pintype "passive"))
    )
    (net (code "81") (name "/RDE") (class "Default")
      (node (ref "R49") (pin "2") (pinfunction "2_2") (pintype "passive"))
      (node (ref "U41") (pin "5") (pinfunction "~{RE}_5") (pintype "input"))
      (node (ref "U41") (pin "6") (pinfunction "DE_6") (pintype "input"))
    )
    (net (code "82") (name "/RF_ANT") (class "Default")
      (node (ref "A11") (pin "1") (pinfunction "RF_1") (pintype "passive"))
      (node (ref "U71") (pin "16") (pinfunction "ANT_16") (pintype "passive"))
    )
    (net (code "83") (name "/RF_MISO") (class "Default")
      (node (ref "U3") (pin "56") (pinfunction "PB4_56") (pintype "bidirectional"))
      (node (ref "U71") (pin "2") (pinfunction "MISO_2") (pintype "passive"))
    )
    (net (code "84") (name "/RF_MOSI") (class "Default")
      (node (ref "U3") (pin "57") (pinfunction "PB5_57") (pintype "bidirectional"))
      (node (ref "U71") (pin "3") (pinfunction "MOSI_3") (pintype "passive"))
    )
    (net (code "85") (name "/RF_NSS") (class "Default")
      (node (ref "U3") (pin "58") (pinfunction "PB6_58") (pintype "bidirectional"))
      (node (ref "U71") (pin "5") (pinfunction "NSS_5") (pintype "passive"))
    )
    (net (code "86") (name "/RF_RESET") (class "Default")
      (node (ref "U3") (pin "59") (pinfunction "PB7_59") (pintype "bidirectional"))
      (node (ref "U71") (pin "6") (pinfunction "RST_6") (pintype "passive"))
    )
    (net (code "87") (name "/RF_SCK") (class "Default")
      (node (ref "U3") (pin "55") (pinfunction "PB3_55") (pintype "bidirectional"))
      (node (ref "U71") (pin "4") (pinfunction "SCK_4") (pintype "passive"))
    )
    (net (code "88") (name "/RS485D") (class "Default")
      (node (ref "R49") (pin "1") (pinfunction "1_1") (pintype "passive"))
      (node (ref "U3") (pin "41") (pinfunction "PA8_41") (pintype "bidirectional"))
    )
    (net (code "89") (name "/RS485_1A") (class "Default")
      (node (ref "D42") (pin "2") (pinfunction "IO2_2") (pintype "passive"))
      (node (ref "R42") (pin "2") (pinfunction "2_2") (pintype "passive"))
      (node (ref "R45") (pin "2") (pinfunction "2_2") (pintype "passive"))
      (node (ref "Sensor") (pin "4") (pinfunction "4_4") (pintype "passive"))
    )
    (net (code "90") (name "/RS485_1B") (class "Default")
      (node (ref "D42") (pin "1") (pinfunction "IO1_1") (pintype "passive"))
      (node (ref "R41") (pin "1") (pinfunction "1_1") (pintype "passive"))
      (node (ref "R44") (pin "2") (pinfunction "2_2") (pintype "passive"))
      (node (ref "Sensor") (pin "3") (pinfunction "3_3") (pintype "passive"))
    )
    (net (code "91") (name "/RS485_SS") (class "Default")
      (node (ref "R43") (pin "2") (pinfunction "2_2") (pintype "passive"))
      (node (ref "U3") (pin "20") (pinfunction "PA4_20") (pintype "bidirectional"))
      (node (ref "U4") (pin "2") (pinfunction "~{RE}_2") (pintype "passive"))
      (node (ref "U4") (pin "3") (pinfunction "DE_3") (pintype "passive"))
    )
    (net (code "92") (name "/RxD") (class "Default")
      (node (ref "R48") (pin "2") (pinfunction "2_2") (pintype "passive"))
      (node (ref "U41") (pin "4") (pinfunction "RxD_4") (pintype "output"))
    )
    (net (code "93") (name "/SWCLK") (class "Default")
      (node (ref "SWD") (pin "3") (pinfunction "3_3") (pintype "passive"))
      (node (ref "U3") (pin "49") (pinfunction "PA14_49") (pintype "bidirectional"))
    )
    (net (code "94") (name "/SWDIO") (class "Default")
      (node (ref "SWD") (pin "2") (pinfunction "2_2") (pintype "passive"))
      (node (ref "U3") (pin "46") (pinfunction "PA13_46") (pintype "bidirectional"))
    )
    (net (code "96") (name "/TxD") (class "Default")
      (node (ref "R410") (pin "2") (pinfunction "2_2") (pintype "passive"))
      (node (ref "U41") (pin "7") (pinfunction "TxD_7") (pintype "input"))
    )
    (net (code "97") (name "/UART3_RX") (class "Default")
      (node (ref "E32_1W") (pin "4") (pinfunction "4_4") (pintype "passive"))
      (node (ref "U3") (pin "30") (pinfunction "PB11_30") (pintype "bidirectional"))
    )
    (net (code "98") (name "/UART3_TX") (class "Default")
      (node (ref "E32_1W") (pin "5") (pinfunction "5_5") (pintype "passive"))
      (node (ref "U3") (pin "29") (pinfunction "PB10_29") (pintype "bidirectional"))
    )
    (net (code "99") (name "/USART1_RX") (class "Default")
      (node (ref "R48") (pin "1") (pinfunction "1_1") (pintype "passive"))
      (node (ref "U3") (pin "43") (pinfunction "PA10_43") (pintype "bidirectional"))
    )
    (net (code "100") (name "/USART1_TX") (class "Default")
      (node (ref "R410") (pin "1") (pinfunction "1_1") (pintype "passive"))
      (node (ref "U3") (pin "42") (pinfunction "PA9_42") (pintype "bidirectional"))
    )
    (net (code "101") (name "/USART2_RX") (class "Default")
      (node (ref "U3") (pin "17") (pinfunction "PA3_17") (pintype "bidirectional"))
      (node (ref "U4") (pin "1") (pinfunction "RO_1") (pintype "passive"))
    )
    (net (code "102") (name "/USART2_TX") (class "Default")
      (node (ref "U3") (pin "16") (pinfunction "PA2_16") (pintype "bidirectional"))
      (node (ref "U4") (pin "4") (pinfunction "DI_4") (pintype "passive"))
    )
    (net (code "103") (name "/VISO") (class "Default")
      (node (ref "C45") (pin "2") (pinfunction "2_2") (pintype "passive"))
      (node (ref "C46") (pin "2") (pinfunction "2_2") (pintype "passive"))
      (node (ref "C47") (pin "2") (pinfunction "2_2") (pintype "passive"))
      (node (ref "C48") (pin "2") (pinfunction "2_2") (pintype "passive"))
      (node (ref "U41") (pin "12") (pinfunction "Viso_12") (pintype "power_in"))
      (node (ref "U41") (pin "19") (pinfunction "Visoi_19") (pintype "power_in"))
      (node (ref "VISO") (pin "1") (pintype "passive"))
    )
    (net (code "104") (name "/Vin") (class "Default")
      (node (ref "D01") (pin "A") (pinfunction "A_A") (pintype "passive"))
      (node (ref "D3") (pin "1") (pinfunction "1_1") (pintype "passive"))
      (node (ref "F1") (pin "2") (pinfunction "2_2") (pintype "passive"))
    )
    (net (code "105") (name "/WKUP_PA0") (class "Default")
      (node (ref "U3") (pin "14") (pinfunction "PA0-WKUP_14") (pintype "bidirectional"))
    )
    (net (code "106") (name "GND") (class "Default")
      (node (ref "24V_IN") (pin "2") (pinfunction "2_2") (pintype "passive"))
      (node (ref "A11") (pin "2") (pinfunction "G_2") (pintype "passive"))
      (node (ref "C01") (pin "2") (pinfunction "2_2") (pintype "passive"))
      (node (ref "C02") (pin "1") (pinfunction "1_1") (pintype "passive"))
      (node (ref "C03") (pin "2") (pinfunction "2_2") (pintype "passive"))
      (node (ref "C04") (pin "1") (pinfunction "1_1") (pintype "passive"))
      (node (ref "C05") (pin "2") (pinfunction "2_2") (pintype "passive"))
      (node (ref "C31") (pin "1") (pinfunction "1_1") (pintype "passive"))
      (node (ref "C32") (pin "1") (pinfunction "1_1") (pintype "passive"))
      (node (ref "C33") (pin "1") (pinfunction "1_1") (pintype "passive"))
      (node (ref "C34") (pin "1") (pinfunction "1_1") (pintype "passive"))
      (node (ref "C35") (pin "1") (pinfunction "1_1") (pintype "passive"))
      (node (ref "C36") (pin "1") (pinfunction "1_1") (pintype "passive"))
      (node (ref "C37") (pin "1") (pinfunction "1_1") (pintype "passive"))
      (node (ref "C41") (pin "1") (pinfunction "1_1") (pintype "passive"))
      (node (ref "C42") (pin "1") (pinfunction "1_1") (pintype "passive"))
      (node (ref "C43") (pin "1") (pinfunction "1_1") (pintype "passive"))
      (node (ref "C44") (pin "1") (pinfunction "1_1") (pintype "passive"))
      (node (ref "C49") (pin "2") (pinfunction "2_2") (pintype "passive"))
      (node (ref "C51") (pin "1") (pinfunction "1_1") (pintype "passive"))
      (node (ref "C52") (pin "1") (pinfunction "1_1") (pintype "passive"))
      (node (ref "C53") (pin "1") (pinfunction "1_1") (pintype "passive"))
      (node (ref "C54") (pin "1") (pinfunction "1_1") (pintype "passive"))
      (node (ref "C55") (pin "1") (pinfunction "1_1") (pintype "passive"))
      (node (ref "C71") (pin "1") (pinfunction "1_1") (pintype "passive"))
      (node (ref "D02") (pin "A") (pinfunction "A_A") (pintype "passive"))
      (node (ref "D3") (pin "2") (pinfunction "2_2") (pintype "passive"))
      (node (ref "D42") (pin "3") (pinfunction "GND_3") (pintype "passive"))
      (node (ref "E32_1W") (pin "1") (pinfunction "1_1") (pintype "passive"))
      (node (ref "E32_1W") (pin "6") (pinfunction "6_6") (pintype "passive"))
      (node (ref "E32_1W") (pin "7") (pinfunction "7_7") (pintype "passive"))
      (node (ref "GND") (pin "1") (pintype "passive"))
      (node (ref "LAMP1") (pin "1") (pinfunction "1_1") (pintype "passive"))
      (node (ref "LAMP2") (pin "1") (pinfunction "1_1") (pintype "passive"))
      (node (ref "LED") (pin "K") (pinfunction "K_K") (pintype "passive"))
      (node (ref "R42") (pin "1") (pinfunction "1_1") (pintype "passive"))
      (node (ref "R43") (pin "1") (pinfunction "1_1") (pintype "passive"))
      (node (ref "SW1") (pin "2") (pinfunction "2_2") (pintype "passive"))
      (node (ref "SW1") (pin "3") (pinfunction "3_3") (pintype "passive"))
      (node (ref "SW2") (pin "2") (pinfunction "2_2") (pintype "passive"))
      (node (ref "SW2") (pin "3") (pinfunction "3_3") (pintype "passive"))
      (node (ref "SWD") (pin "1") (pinfunction "1_1") (pintype "passive"))
      (node (ref "Sensor") (pin "2") (pinfunction "2_2") (pintype "passive"))
      (node (ref "U1") (pin "3") (pinfunction "GND_3") (pintype "power_in"))
      (node (ref "U1") (pin "5") (pinfunction "~{ON}/OFF_5") (pintype "input"))
      (node (ref "U1") (pin "6") (pinfunction "TAB_6") (pintype "power_in"))
      (node (ref "U12") (pin "1") (pinfunction "GND_1") (pintype "power_in"))
      (node (ref "U3") (pin "12") (pinfunction "VSSA_12") (pintype "power_in"))
      (node (ref "U3") (pin "18") (pinfunction "VSS_4_18") (pintype "power_in"))
      (node (ref "U3") (pin "31") (pinfunction "VSS_1_31") (pintype "power_in"))
      (node (ref "U3") (pin "47") (pinfunction "VSS_2_47") (pintype "power_in"))
      (node (ref "U3") (pin "60") (pinfunction "BOOT0_60") (pintype "input"))
      (node (ref "U3") (pin "63") (pinfunction "VSS_3_63") (pintype "power_in"))
      (node (ref "U32") (pin "9") (pinfunction "GND_9") (pintype "power_in"))
      (node (ref "U4") (pin "5") (pinfunction "GND_5") (pintype "passive"))
      (node (ref "U41") (pin "1") (pinfunction "GND1_1") (pintype "power_in"))
      (node (ref "U41") (pin "10") (pinfunction "GND1_10") (pintype "power_in"))
      (node (ref "U41") (pin "3") (pinfunction "GND1_3") (pintype "power_in"))
      (node (ref "U41") (pin "9") (pinfunction "GND1_9") (pintype "power_in"))
      (node (ref "U51") (pin "1") (pinfunction "GND_1") (pintype "passive"))
      (node (ref "U71") (pin "1") (pinfunction "GND_1") (pintype "passive"))
      (node (ref "U71") (pin "15") (pinfunction "GND_15") (pintype "passive"))
      (node (ref "U71") (pin "8") (pinfunction "GND_8") (pintype "passive"))
    )
    (net (code "107") (name "GND_ISO") (class "Default")
      (node (ref "C45") (pin "1") (pinfunction "1_1") (pintype "passive"))
      (node (ref "C46") (pin "1") (pinfunction "1_1") (pintype "passive"))
      (node (ref "C47") (pin "1") (pinfunction "1_1") (pintype "passive"))
      (node (ref "C48") (pin "1") (pinfunction "1_1") (pintype "passive"))
      (node (ref "D41") (pin "3") (pinfunction "GND_3") (pintype "passive"))
      (node (ref "GND_ISO") (pin "1") (pintype "passive"))
      (node (ref "U41") (pin "11") (pinfunction "GND2_11") (pintype "power_in"))
      (node (ref "U41") (pin "14") (pinfunction "GND2_14") (pintype "power_in"))
      (node (ref "U41") (pin "16") (pinfunction "GND2_16") (pintype "power_in"))
      (node (ref "U41") (pin "20") (pinfunction "GND2_20") (pintype "power_in"))
    )
    (net (code "108") (name "Net-(24V_IN-Pad1)") (class "Default")
      (node (ref "24V_IN") (pin "1") (pinfunction "1_1") (pintype "passive"))
      (node (ref "F1") (pin "1") (pinfunction "1_1") (pintype "passive"))
    )
    (net (code "109") (name "Net-(LED-PadA)") (class "Default")
      (node (ref "LED") (pin "A") (pinfunction "A_A") (pintype "passive"))
      (node (ref "R01") (pin "1") (pinfunction "1_1") (pintype "passive"))
    )
    (net (code "110") (name "Net-(U1-OUT)") (class "Default")
      (node (ref "D02") (pin "K") (pinfunction "K_K") (pintype "passive"))
      (node (ref "L01") (pin "1") (pinfunction "1_1") (pintype "passive"))
      (node (ref "U1") (pin "2") (pinfunction "OUT_2") (pintype "power_in"))
    )
    (net (code "111") (name "Net-(U4-A)") (class "Default")
      (node (ref "R45") (pin "1") (pinfunction "1_1") (pintype "passive"))
      (node (ref "U4") (pin "6") (pinfunction "A_6") (pintype "passive"))
    )
    (net (code "112") (name "Net-(U4-B)") (class "Default")
      (node (ref "R44") (pin "1") (pinfunction "1_1") (pintype "passive"))
      (node (ref "U4") (pin "7") (pinfunction "B_7") (pintype "passive"))
    )
    (net (code "113") (name "VCC") (class "Default")
      (node (ref "C05") (pin "1") (pinfunction "1_1") (pintype "passive"))
      (node (ref "C33") (pin "2") (pinfunction "2_2") (pintype "passive"))
      (node (ref "C34") (pin "2") (pinfunction "2_2") (pintype "passive"))
      (node (ref "C35") (pin "2") (pinfunction "2_2") (pintype "passive"))
      (node (ref "C36") (pin "2") (pinfunction "2_2") (pintype "passive"))
      (node (ref "C37") (pin "2") (pinfunction "2_2") (pintype "passive"))
      (node (ref "C71") (pin "2") (pinfunction "2_2") (pintype "passive"))
      (node (ref "R31") (pin "2") (pinfunction "2_2") (pintype "passive"))
      (node (ref "R32") (pin "2") (pinfunction "2_2") (pintype "passive"))
      (node (ref "R33") (pin "2") (pinfunction "2_2") (pintype "passive"))
      (node (ref "U12") (pin "2") (pinfunction "OUT_2") (pintype "power_in"))
      (node (ref "U12") (pin "4") (pinfunction "4_4") (pintype "passive"))
      (node (ref "U3") (pin "13") (pinfunction "VDDA_13") (pintype "power_in"))
      (node (ref "U3") (pin "19") (pinfunction "VDD_4_19") (pintype "power_in"))
      (node (ref "U3") (pin "32") (pinfunction "VDD_1_32") (pintype "power_in"))
      (node (ref "U3") (pin "48") (pinfunction "VDD_2_48") (pintype "power_in"))
      (node (ref "U3") (pin "64") (pinfunction "VDD_3_64") (pintype "power_in"))
      (node (ref "U71") (pin "12") (pinfunction "+3V3_12") (pintype "passive"))
    )
    (net (code "114") (name "unconnected-(DryOut-Pad1)") (class "Default")
      (node (ref "DryOut") (pin "1") (pinfunction "1_1") (pintype "passive"))
    )
    (net (code "115") (name "unconnected-(DryOut-Pad2)") (class "Default")
      (node (ref "DryOut") (pin "2") (pinfunction "2_2") (pintype "passive"))
    )
    (net (code "116") (name "unconnected-(DryOut-Pad8)") (class "Default")
      (node (ref "DryOut") (pin "8") (pinfunction "8_8") (pintype "passive"))
    )
    (net (code "117") (name "unconnected-(DryOut-Pad11)") (class "Default")
      (node (ref "DryOut") (pin "11") (pinfunction "11_11") (pintype "passive"))
    )
    (net (code "118") (name "unconnected-(DryOut-Pad12)") (class "Default")
      (node (ref "DryOut") (pin "12") (pinfunction "12_12") (pintype "passive"))
    )
    (net (code "119") (name "unconnected-(DryOut-Pad18)") (class "Default")
      (node (ref "DryOut") (pin "18") (pinfunction "18_18") (pintype "passive"))
    )
    (net (code "120") (name "unconnected-(RL1-Pad3)") (class "Default")
      (node (ref "RL1") (pin "3") (pinfunction "3_3") (pintype "passive"))
    )
    (net (code "121") (name "unconnected-(RL1-Pad4)") (class "Default")
      (node (ref "RL1") (pin "4") (pinfunction "4_4") (pintype "passive"))
    )
    (net (code "122") (name "unconnected-(RL2-Pad3)") (class "Default")
      (node (ref "RL2") (pin "3") (pinfunction "3_3") (pintype "passive"))
    )
    (net (code "123") (name "unconnected-(RL2-Pad4)") (class "Default")
      (node (ref "RL2") (pin "4") (pinfunction "4_4") (pintype "passive"))
    )
    (net (code "124") (name "unconnected-(RL3-Pad3)") (class "Default")
      (node (ref "RL3") (pin "3") (pinfunction "3_3") (pintype "passive"))
    )
    (net (code "125") (name "unconnected-(RL3-Pad4)") (class "Default")
      (node (ref "RL3") (pin "4") (pinfunction "4_4") (pintype "passive"))
    )
    (net (code "126") (name "unconnected-(RL4-Pad3)") (class "Default")
      (node (ref "RL4") (pin "3") (pinfunction "3_3") (pintype "passive"))
    )
    (net (code "127") (name "unconnected-(RL4-Pad4)") (class "Default")
      (node (ref "RL4") (pin "4") (pinfunction "4_4") (pintype "passive"))
    )
    (net (code "128") (name "unconnected-(RL5-Pad3)") (class "Default")
      (node (ref "RL5") (pin "3") (pinfunction "3_3") (pintype "passive"))
    )
    (net (code "129") (name "unconnected-(RL5-Pad4)") (class "Default")
      (node (ref "RL5") (pin "4") (pinfunction "4_4") (pintype "passive"))
    )
    (net (code "130") (name "unconnected-(RL6-Pad3)") (class "Default")
      (node (ref "RL6") (pin "3") (pinfunction "3_3") (pintype "passive"))
    )
    (net (code "131") (name "unconnected-(RL6-Pad4)") (class "Default")
      (node (ref "RL6") (pin "4") (pinfunction "4_4") (pintype "passive"))
    )
    (net (code "132") (name "unconnected-(RL7-Pad3)") (class "Default")
      (node (ref "RL7") (pin "3") (pinfunction "3_3") (pintype "passive"))
    )
    (net (code "133") (name "unconnected-(RL7-Pad4)") (class "Default")
      (node (ref "RL7") (pin "4") (pinfunction "4_4") (pintype "passive"))
    )
    (net (code "134") (name "unconnected-(RL8-Pad1)") (class "Default")
      (node (ref "RL8") (pin "1") (pinfunction "1_1") (pintype "passive"))
    )
    (net (code "135") (name "unconnected-(RL8-Pad4)") (class "Default")
      (node (ref "RL8") (pin "4") (pinfunction "4_4") (pintype "passive"))
    )
    (net (code "136") (name "unconnected-(U3A-PA12-Pad45)") (class "Default")
      (node (ref "U3") (pin "45") (pinfunction "PA12_45") (pintype "bidirectional"))
    )
    (net (code "137") (name "unconnected-(U3A-PB8-Pad61)") (class "Default")
      (node (ref "U3") (pin "61") (pinfunction "PB8_61") (pintype "bidirectional"))
    )
    (net (code "138") (name "unconnected-(U3A-PB14-Pad35)") (class "Default")
      (node (ref "U3") (pin "35") (pinfunction "PB14_35") (pintype "bidirectional"))
    )
    (net (code "139") (name "unconnected-(U3A-PB15-Pad36)") (class "Default")
      (node (ref "U3") (pin "36") (pinfunction "PB15_36") (pintype "bidirectional"))
    )
    (net (code "140") (name "unconnected-(U3A-PC6-Pad37)") (class "Default")
      (node (ref "U3") (pin "37") (pinfunction "PC6_37") (pintype "bidirectional"))
    )
    (net (code "141") (name "unconnected-(U3A-PC7-Pad38)") (class "Default")
      (node (ref "U3") (pin "38") (pinfunction "PC7_38") (pintype "bidirectional"))
    )
    (net (code "142") (name "unconnected-(U3A-PC8-Pad39)") (class "Default")
      (node (ref "U3") (pin "39") (pinfunction "PC8_39") (pintype "bidirectional"))
    )
    (net (code "143") (name "unconnected-(U3A-PC9-Pad40)") (class "Default")
      (node (ref "U3") (pin "40") (pinfunction "PC9_40") (pintype "bidirectional"))
    )
    (net (code "144") (name "unconnected-(U3A-PC10-Pad51)") (class "Default")
      (node (ref "U3") (pin "51") (pinfunction "PC10_51") (pintype "bidirectional"))
    )
    (net (code "145") (name "unconnected-(U3A-PC11-Pad52)") (class "Default")
      (node (ref "U3") (pin "52") (pinfunction "PC11_52") (pintype "bidirectional"))
    )
    (net (code "146") (name "unconnected-(U3A-PC12-Pad53)") (class "Default")
      (node (ref "U3") (pin "53") (pinfunction "PC12_53") (pintype "bidirectional"))
    )
    (net (code "147") (name "unconnected-(U3A-PC13-TAMPER-RTC-Pad2)") (class "Default")
      (node (ref "U3") (pin "2") (pinfunction "PC13-TAMPER-RTC_2") (pintype "bidirectional"))
    )
    (net (code "148") (name "unconnected-(U3A-PC14-OSC32_IN-Pad3)") (class "Default")
      (node (ref "U3") (pin "3") (pinfunction "PC14-OSC32_IN_3") (pintype "bidirectional"))
    )
    (net (code "149") (name "unconnected-(U3A-PC15-OSC32_OUT-Pad4)") (class "Default")
      (node (ref "U3") (pin "4") (pinfunction "PC15-OSC32_OUT_4") (pintype "bidirectional"))
    )
    (net (code "150") (name "unconnected-(U3A-PD2-Pad54)") (class "Default")
      (node (ref "U3") (pin "54") (pinfunction "PD2_54") (pintype "bidirectional"))
    )
    (net (code "151") (name "unconnected-(U3B-VBAT-Pad1)") (class "Default")
      (node (ref "U3") (pin "1") (pinfunction "VBAT_1") (pintype "power_in"))
    )
    (net (code "152") (name "unconnected-(U51-GR5-Pad11)") (class "Default")
      (node (ref "U51") (pin "11") (pinfunction "GR5_11") (pintype "passive"))
    )
    (net (code "153") (name "unconnected-(U51-GR6-Pad10)") (class "Default")
      (node (ref "U51") (pin "10") (pinfunction "GR6_10") (pintype "passive"))
    )
    (net (code "154") (name "unconnected-(U51-K1-Pad19)") (class "Default")
      (node (ref "U51") (pin "19") (pinfunction "K1_19") (pintype "passive"))
    )
    (net (code "155") (name "unconnected-(U51-K2-Pad20)") (class "Default")
      (node (ref "U51") (pin "20") (pinfunction "K2_20") (pintype "passive"))
    )
    (net (code "156") (name "unconnected-(U71-DIO0-Pad11)") (class "Default")
      (node (ref "U71") (pin "11") (pinfunction "DIO0_11") (pintype "passive"))
    )
    (net (code "157") (name "unconnected-(U71-DIO1-Pad10)") (class "Default")
      (node (ref "U71") (pin "10") (pinfunction "DIO1_10") (pintype "passive"))
    )
    (net (code "158") (name "unconnected-(U71-DIO3-Pad14)") (class "Default")
      (node (ref "U71") (pin "14") (pinfunction "DIO3_14") (pintype "passive"))
    )
    (net (code "159") (name "unconnected-(U71-DIO4-Pad13)") (class "Default")
      (node (ref "U71") (pin "13") (pinfunction "DIO4_13") (pintype "passive"))
    )
    (net (code "160") (name "unconnected-(U71-DIO5-Pad7)") (class "Default")
      (node (ref "U71") (pin "7") (pinfunction "DIO5_7") (pintype "passive"))
    )
  )
)
